# SCH_power-distribution_2026-04-19.net
KiCad netlist of a schematic drawn in EasyEDA
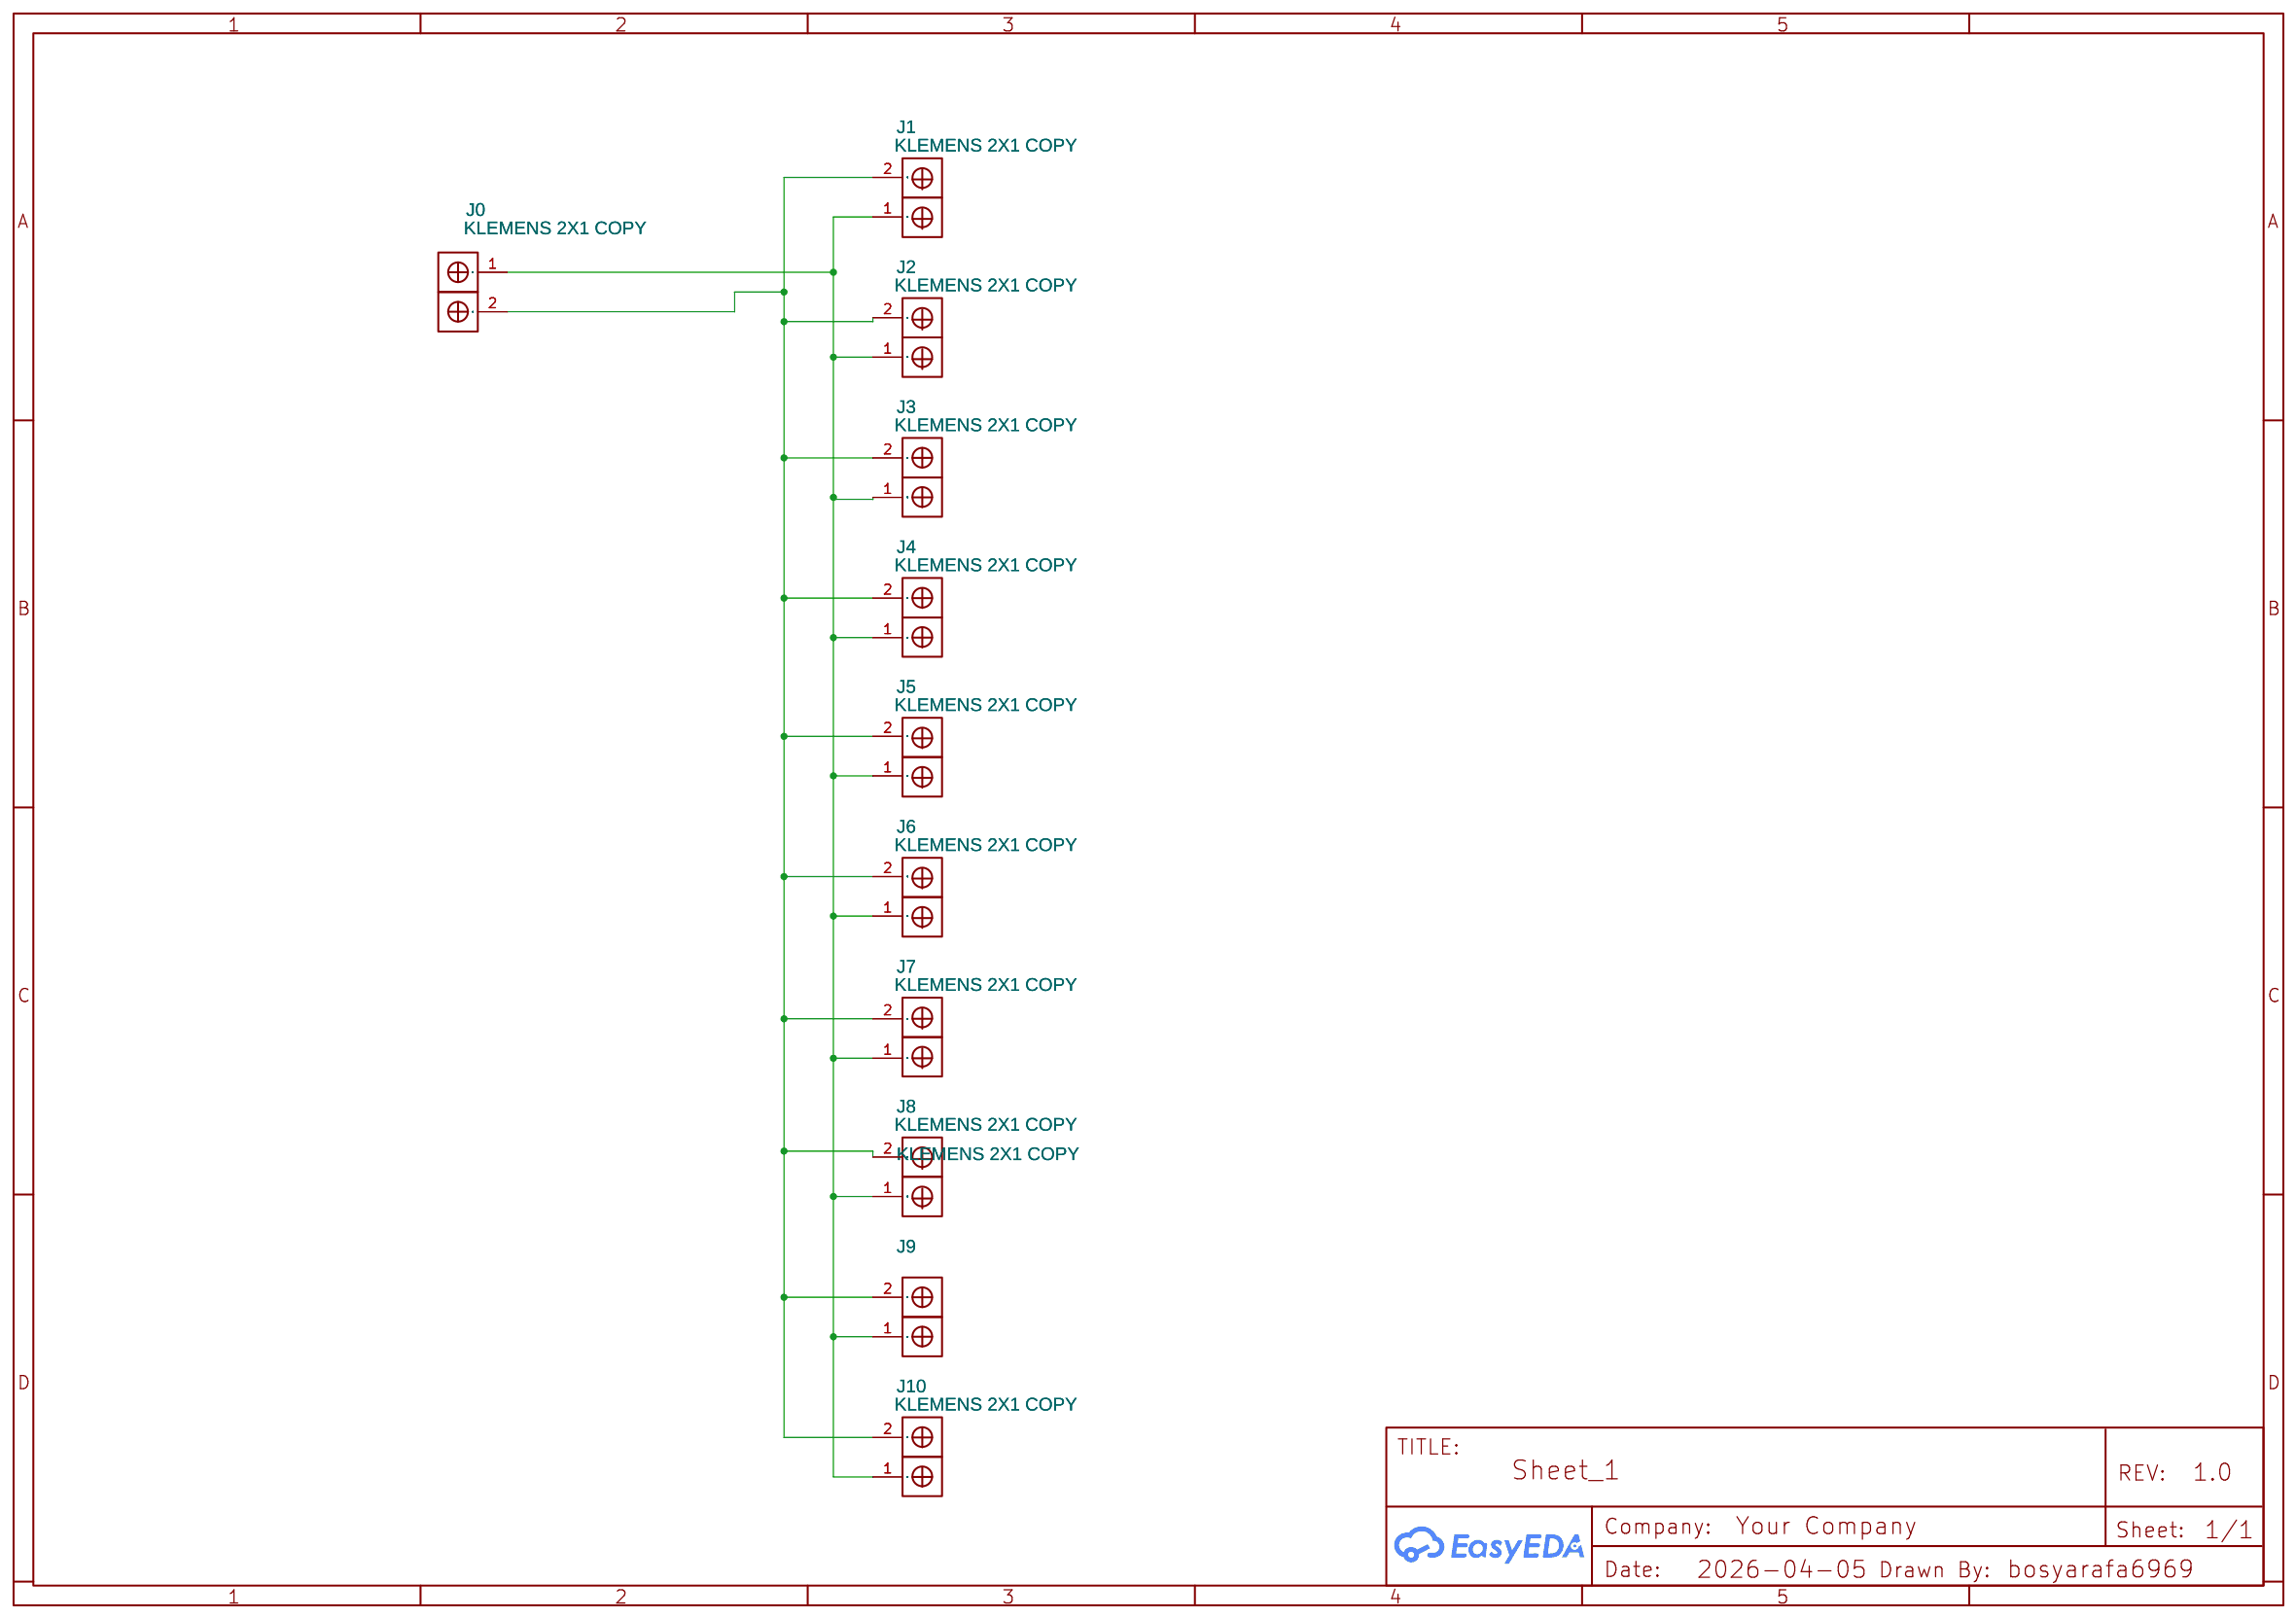
[diagram p0: schematic sheet]

(export (version "E")
  (design (tool "Eeschema 10.0.6"))
  (components
    (comp (ref "J0") (value "KLEMENS 2X1 COPY") (libsource (lib "") (part "KLEMENS 2X1 COPY_7")))
    (comp (ref "J1") (value "KLEMENS 2X1 COPY") (libsource (lib "") (part "KLEMENS 2X1 COPY_5")))
    (comp (ref "J2") (value "KLEMENS 2X1 COPY") (libsource (lib "") (part "KLEMENS 2X1 COPY_2")))
    (comp (ref "J3") (value "KLEMENS 2X1 COPY") (libsource (lib "") (part "KLEMENS 2X1 COPY_8")))
    (comp (ref "J4") (value "KLEMENS 2X1 COPY") (libsource (lib "") (part "KLEMENS 2X1 COPY")))
    (comp (ref "J5") (value "KLEMENS 2X1 COPY") (libsource (lib "") (part "KLEMENS 2X1 COPY_6")))
    (comp (ref "J6") (value "KLEMENS 2X1 COPY") (libsource (lib "") (part "KLEMENS 2X1 COPY_4")))
    (comp (ref "J7") (value "KLEMENS 2X1 COPY") (libsource (lib "") (part "KLEMENS 2X1 COPY_1")))
    (comp (ref "J8") (value "KLEMENS 2X1 COPY") (libsource (lib "") (part "KLEMENS 2X1 COPY_2")))
    (comp (ref "J9") (value "KLEMENS 2X1 COPY") (libsource (lib "") (part "KLEMENS 2X1 COPY_3")))
    (comp (ref "J10") (value "KLEMENS 2X1 COPY") (libsource (lib "") (part "KLEMENS 2X1 COPY")))
  )
  (nets
    (net (code "1") (name "Net-(J0-Gnd)") (class "Default")
      (node (ref "J0") (pin "1") (pinfunction "Gnd_1") (pintype "unspecified"))
      (node (ref "J1") (pin "1") (pinfunction "Gnd_1") (pintype "unspecified"))
      (node (ref "J10") (pin "1") (pinfunction "Gnd_1") (pintype "unspecified"))
      (node (ref "J2") (pin "1") (pinfunction "Gnd_1") (pintype "unspecified"))
      (node (ref "J3") (pin "1") (pinfunction "Gnd_1") (pintype "unspecified"))
      (node (ref "J4") (pin "1") (pinfunction "Gnd_1") (pintype "unspecified"))
      (node (ref "J5") (pin "1") (pinfunction "Gnd_1") (pintype "unspecified"))
      (node (ref "J6") (pin "1") (pinfunction "Gnd_1") (pintype "unspecified"))
      (node (ref "J7") (pin "1") (pinfunction "Gnd_1") (pintype "unspecified"))
      (node (ref "J8") (pin "1") (pinfunction "Gnd_1") (pintype "unspecified"))
      (node (ref "J9") (pin "1") (pinfunction "Gnd_1") (pintype "unspecified"))
    )
    (net (code "2") (name "Net-(J0-Vcc)") (class "Default")
      (node (ref "J0") (pin "2") (pinfunction "Vcc_2") (pintype "unspecified"))
      (node (ref "J1") (pin "2") (pinfunction "Vcc_2") (pintype "unspecified"))
      (node (ref "J10") (pin "2") (pinfunction "Vcc_2") (pintype "unspecified"))
      (node (ref "J2") (pin "2") (pinfunction "Vcc_2") (pintype "unspecified"))
      (node (ref "J3") (pin "2") (pinfunction "Vcc_2") (pintype "unspecified"))
      (node (ref "J4") (pin "2") (pinfunction "Vcc_2") (pintype "unspecified"))
      (node (ref "J5") (pin "2") (pinfunction "Vcc_2") (pintype "unspecified"))
      (node (ref "J6") (pin "2") (pinfunction "Vcc_2") (pintype "unspecified"))
      (node (ref "J7") (pin "2") (pinfunction "Vcc_2") (pintype "unspecified"))
      (node (ref "J8") (pin "2") (pinfunction "Vcc_2") (pintype "unspecified"))
      (node (ref "J9") (pin "2") (pinfunction "Vcc_2") (pintype "unspecified"))
    )
  )
)
